# PET_Diag_Clip.net
KiCad netlist of a schematic drawn in EAGLE
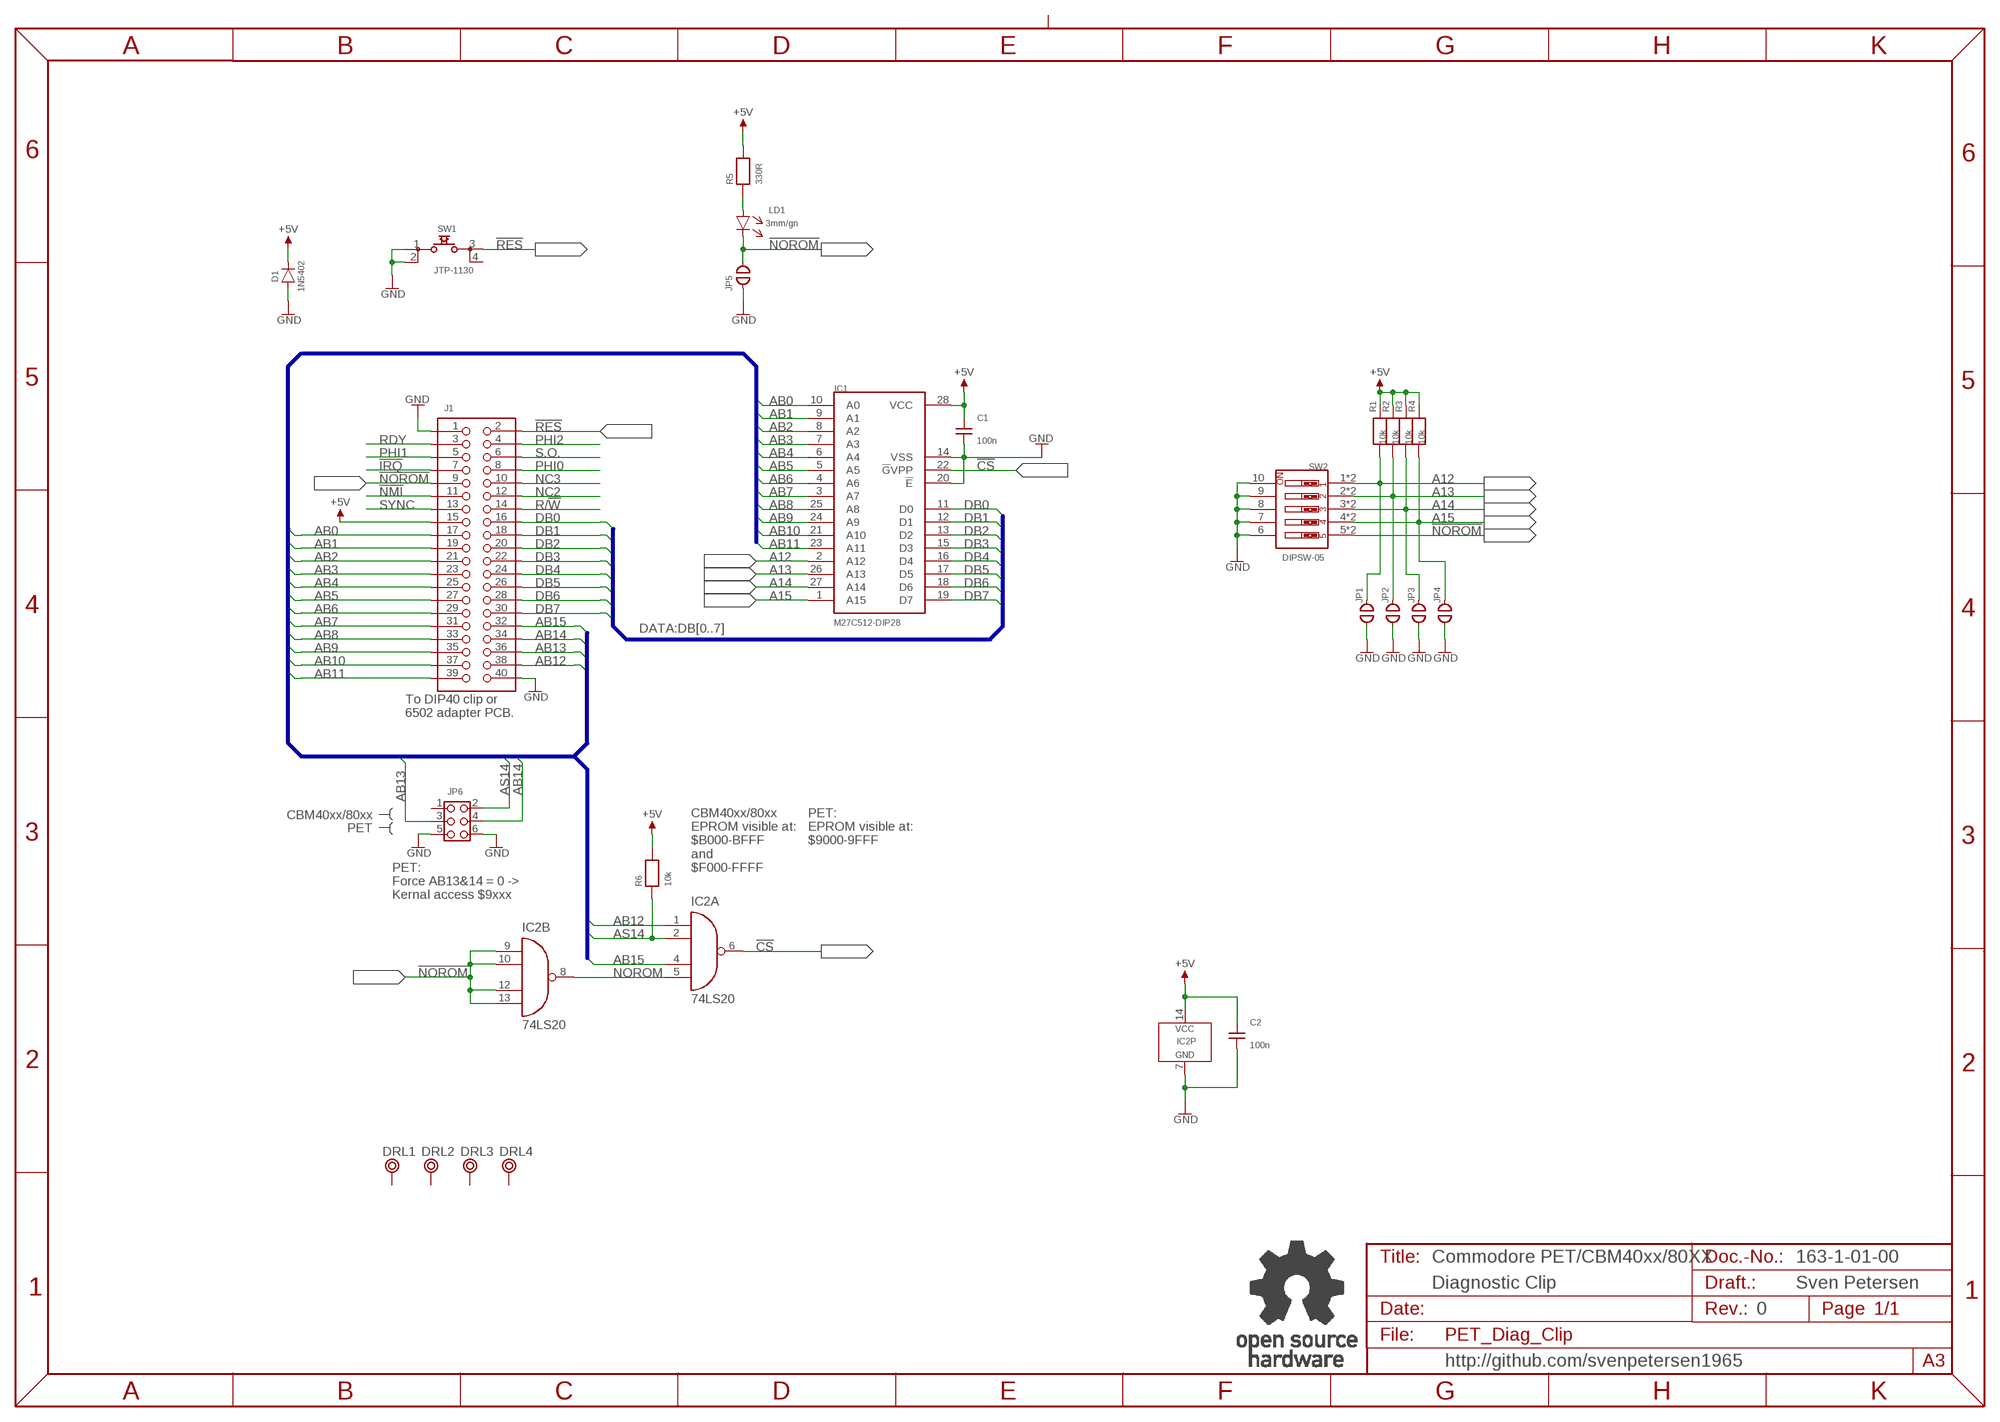
[diagram p0: schematic, sheet 1]

(export (version "E")
  (design (tool "Eeschema 10.0.6"))
  (components
    (comp (ref "C1")
      (value "100n")
      (footprint "eagle-import:C-2,5")
      (libsource (lib "eagle-import") (part "CAP01"))
    )
    (comp (ref "C2")
      (value "100n")
      (footprint "eagle-import:C-2,5")
      (libsource (lib "eagle-import") (part "CAP01"))
    )
    (comp (ref "D1")
      (value "1N5402")
      (footprint "eagle-import:DO-201")
      (libsource (lib "eagle-import") (part "1N5402"))
    )
    (comp (ref "DRL1")
      (value "BOHR3,5")
      (footprint "eagle-import:BOHR3,5")
      (libsource (lib "eagle-import") (part "BOHR3,5"))
    )
    (comp (ref "DRL2")
      (value "BOHR3,5")
      (footprint "eagle-import:BOHR3,5")
      (libsource (lib "eagle-import") (part "BOHR3,5"))
    )
    (comp (ref "DRL3")
      (value "BOHR3,5")
      (footprint "eagle-import:BOHR3,5")
      (libsource (lib "eagle-import") (part "BOHR3,5"))
    )
    (comp (ref "DRL4")
      (value "BOHR3,5")
      (footprint "eagle-import:BOHR3,5")
      (libsource (lib "eagle-import") (part "BOHR3,5"))
    )
    (comp (ref "IC1")
      (value "M27C512-DIP28")
      (footprint "eagle-import:DIL28-6")
      (libsource (lib "eagle-import") (part "M27C512-DIP28"))
    )
    (comp (ref "IC2")
      (value "74LS20")
      (footprint "eagle-import:DIL-14")
      (libsource (lib "eagle-import") (part "7420N"))
    )
    (comp (ref "J1")
      (value "PINHD-2X20WV")
      (footprint "eagle-import:2X20WV")
      (libsource (lib "eagle-import") (part "PINHD-2X20WV"))
    )
    (comp (ref "JP1")
      (value "OPEN")
      (footprint "eagle-import:CP_OP")
      (libsource (lib "eagle-import") (part "OPEN"))
    )
    (comp (ref "JP2")
      (value "OPEN")
      (footprint "eagle-import:CP_OP")
      (libsource (lib "eagle-import") (part "OPEN"))
    )
    (comp (ref "JP3")
      (value "OPEN")
      (footprint "eagle-import:CP_OP")
      (libsource (lib "eagle-import") (part "OPEN"))
    )
    (comp (ref "JP4")
      (value "OPEN")
      (footprint "eagle-import:CP_OP")
      (libsource (lib "eagle-import") (part "OPEN"))
    )
    (comp (ref "JP5")
      (value "COMBI_2P")
      (footprint "eagle-import:COMBI-2P")
      (libsource (lib "eagle-import") (part "COMBI_2P"))
    )
    (comp (ref "JP6")
      (value "JUMPER2X3")
      (footprint "eagle-import:2X03")
      (libsource (lib "eagle-import") (part "JUMPER2X3"))
    )
    (comp (ref "LD1")
      (value "3mm/gn")
      (footprint "eagle-import:3MM")
      (libsource (lib "eagle-import") (part "3MM"))
    )
    (comp (ref "R1")
      (value "10k")
      (footprint "eagle-import:R-10")
      (libsource (lib "eagle-import") (part "RES04"))
    )
    (comp (ref "R2")
      (value "10k")
      (footprint "eagle-import:R-10")
      (libsource (lib "eagle-import") (part "RES04"))
    )
    (comp (ref "R3")
      (value "10k")
      (footprint "eagle-import:R-10")
      (libsource (lib "eagle-import") (part "RES04"))
    )
    (comp (ref "R4")
      (value "10k")
      (footprint "eagle-import:R-10")
      (libsource (lib "eagle-import") (part "RES04"))
    )
    (comp (ref "R5")
      (value "330R")
      (footprint "eagle-import:R-10")
      (libsource (lib "eagle-import") (part "RES04"))
    )
    (comp (ref "R6")
      (value "10k")
      (footprint "eagle-import:R-10")
      (libsource (lib "eagle-import") (part "RES04"))
    )
    (comp (ref "SW1")
      (value "JTP-1130")
      (footprint "eagle-import:JTP-1130")
      (libsource (lib "eagle-import") (part "JTP-1130"))
    )
    (comp (ref "SW2")
      (value "DIPSW-05")
      (footprint "eagle-import:DIPSW-05VJ")
      (libsource (lib "eagle-import") (part "DIPSW-05"))
    )
    (comp (ref "U$13")
      (value "OPEN_SOURCE_HW")
      (footprint "eagle-import:OPENHW")
      (libsource (lib "eagle-import") (part "OPEN_SOURCE_HW"))
    )
  )
  (nets
    (net (code "9") (name "+5V") (class "Default")
      (node (ref "C1") (pin "2") (pinfunction "2_2") (pintype "passive"))
      (node (ref "C2") (pin "2") (pinfunction "2_2") (pintype "passive"))
      (node (ref "D1") (pin "K") (pinfunction "K_K") (pintype "passive"))
      (node (ref "IC1") (pin "28") (pinfunction "VCC_28") (pintype "power_in"))
      (node (ref "IC2") (pin "14") (pinfunction "VCC_14") (pintype "bidirectional"))
      (node (ref "J1") (pin "15") (pinfunction "15_15") (pintype "passive"))
      (node (ref "R1") (pin "1") (pinfunction "1_1") (pintype "passive"))
      (node (ref "R2") (pin "1") (pinfunction "1_1") (pintype "passive"))
      (node (ref "R3") (pin "1") (pinfunction "1_1") (pintype "passive"))
      (node (ref "R4") (pin "1") (pinfunction "1_1") (pintype "passive"))
      (node (ref "R5") (pin "2") (pinfunction "2_2") (pintype "passive"))
      (node (ref "R6") (pin "2") (pinfunction "2_2") (pintype "passive"))
    )
    (net (code "10") (name "/A12") (class "Default")
      (node (ref "IC1") (pin "2") (pinfunction "A12_2") (pintype "input"))
      (node (ref "JP1") (pin "2") (pinfunction "2_2") (pintype "passive"))
      (node (ref "R1") (pin "2") (pinfunction "2_2") (pintype "passive"))
      (node (ref "SW2") (pin "1") (pinfunction "1_1") (pintype "passive"))
      (node (ref "SW2") (pin "1J") (pinfunction "1_1J") (pintype "passive"))
    )
    (net (code "11") (name "/A13") (class "Default")
      (node (ref "IC1") (pin "26") (pinfunction "A13_26") (pintype "input"))
      (node (ref "JP2") (pin "2") (pinfunction "2_2") (pintype "passive"))
      (node (ref "R2") (pin "2") (pinfunction "2_2") (pintype "passive"))
      (node (ref "SW2") (pin "2") (pinfunction "2_2") (pintype "passive"))
      (node (ref "SW2") (pin "2J") (pinfunction "2_2J") (pintype "passive"))
    )
    (net (code "12") (name "/A14") (class "Default")
      (node (ref "IC1") (pin "27") (pinfunction "A14_27") (pintype "input"))
      (node (ref "JP3") (pin "2") (pinfunction "2_2") (pintype "passive"))
      (node (ref "R3") (pin "2") (pinfunction "2_2") (pintype "passive"))
      (node (ref "SW2") (pin "3") (pinfunction "3_3") (pintype "passive"))
      (node (ref "SW2") (pin "3J") (pinfunction "3_3J") (pintype "passive"))
    )
    (net (code "13") (name "/A15") (class "Default")
      (node (ref "IC1") (pin "1") (pinfunction "A15_1") (pintype "input"))
      (node (ref "JP4") (pin "2") (pinfunction "2_2") (pintype "passive"))
      (node (ref "R4") (pin "2") (pinfunction "2_2") (pintype "passive"))
      (node (ref "SW2") (pin "4") (pinfunction "4_4") (pintype "passive"))
      (node (ref "SW2") (pin "4J") (pinfunction "4_4J") (pintype "passive"))
    )
    (net (code "14") (name "/AB0") (class "Default")
      (node (ref "IC1") (pin "10") (pinfunction "A0_10") (pintype "input"))
      (node (ref "J1") (pin "17") (pinfunction "17_17") (pintype "passive"))
    )
    (net (code "15") (name "/AB1") (class "Default")
      (node (ref "IC1") (pin "9") (pinfunction "A1_9") (pintype "input"))
      (node (ref "J1") (pin "19") (pinfunction "19_19") (pintype "passive"))
    )
    (net (code "16") (name "/AB2") (class "Default")
      (node (ref "IC1") (pin "8") (pinfunction "A2_8") (pintype "input"))
      (node (ref "J1") (pin "21") (pinfunction "21_21") (pintype "passive"))
    )
    (net (code "17") (name "/AB3") (class "Default")
      (node (ref "IC1") (pin "7") (pinfunction "A3_7") (pintype "input"))
      (node (ref "J1") (pin "23") (pinfunction "23_23") (pintype "passive"))
    )
    (net (code "18") (name "/AB4") (class "Default")
      (node (ref "IC1") (pin "6") (pinfunction "A4_6") (pintype "input"))
      (node (ref "J1") (pin "25") (pinfunction "25_25") (pintype "passive"))
    )
    (net (code "19") (name "/AB5") (class "Default")
      (node (ref "IC1") (pin "5") (pinfunction "A5_5") (pintype "input"))
      (node (ref "J1") (pin "27") (pinfunction "27_27") (pintype "passive"))
    )
    (net (code "20") (name "/AB6") (class "Default")
      (node (ref "IC1") (pin "4") (pinfunction "A6_4") (pintype "input"))
      (node (ref "J1") (pin "29") (pinfunction "29_29") (pintype "passive"))
    )
    (net (code "21") (name "/AB7") (class "Default")
      (node (ref "IC1") (pin "3") (pinfunction "A7_3") (pintype "input"))
      (node (ref "J1") (pin "31") (pinfunction "31_31") (pintype "passive"))
    )
    (net (code "22") (name "/AB8") (class "Default")
      (node (ref "IC1") (pin "25") (pinfunction "A8_25") (pintype "input"))
      (node (ref "J1") (pin "33") (pinfunction "33_33") (pintype "passive"))
    )
    (net (code "23") (name "/AB9") (class "Default")
      (node (ref "IC1") (pin "24") (pinfunction "A9_24") (pintype "input"))
      (node (ref "J1") (pin "35") (pinfunction "35_35") (pintype "passive"))
    )
    (net (code "24") (name "/AB10") (class "Default")
      (node (ref "IC1") (pin "21") (pinfunction "A10_21") (pintype "input"))
      (node (ref "J1") (pin "37") (pinfunction "37_37") (pintype "passive"))
    )
    (net (code "25") (name "/AB11") (class "Default")
      (node (ref "IC1") (pin "23") (pinfunction "A11_23") (pintype "input"))
      (node (ref "J1") (pin "39") (pinfunction "39_39") (pintype "passive"))
    )
    (net (code "26") (name "/AB12") (class "Default")
      (node (ref "IC2") (pin "1") (pinfunction "I0_1") (pintype "input"))
      (node (ref "J1") (pin "38") (pinfunction "38_38") (pintype "passive"))
    )
    (net (code "27") (name "/AB13") (class "Default")
      (node (ref "J1") (pin "36") (pinfunction "36_36") (pintype "passive"))
      (node (ref "JP6") (pin "3") (pinfunction "3_3") (pintype "bidirectional"))
    )
    (net (code "28") (name "/AB14") (class "Default")
      (node (ref "J1") (pin "34") (pinfunction "34_34") (pintype "passive"))
      (node (ref "JP6") (pin "4") (pinfunction "4_4") (pintype "bidirectional"))
    )
    (net (code "29") (name "/AB15") (class "Default")
      (node (ref "IC2") (pin "4") (pinfunction "I2_4") (pintype "input"))
      (node (ref "J1") (pin "32") (pinfunction "32_32") (pintype "passive"))
    )
    (net (code "30") (name "/AS14") (class "Default")
      (node (ref "IC2") (pin "2") (pinfunction "I1_2") (pintype "input"))
      (node (ref "JP6") (pin "2") (pinfunction "2_2") (pintype "bidirectional"))
      (node (ref "R6") (pin "1") (pinfunction "1_1") (pintype "passive"))
    )
    (net (code "32") (name "/DB0") (class "Default")
      (node (ref "IC1") (pin "11") (pinfunction "D0_11") (pintype "bidirectional"))
      (node (ref "J1") (pin "16") (pinfunction "16_16") (pintype "passive"))
    )
    (net (code "33") (name "/DB1") (class "Default")
      (node (ref "IC1") (pin "12") (pinfunction "D1_12") (pintype "bidirectional"))
      (node (ref "J1") (pin "18") (pinfunction "18_18") (pintype "passive"))
    )
    (net (code "34") (name "/DB2") (class "Default")
      (node (ref "IC1") (pin "13") (pinfunction "D2_13") (pintype "bidirectional"))
      (node (ref "J1") (pin "20") (pinfunction "20_20") (pintype "passive"))
    )
    (net (code "35") (name "/DB3") (class "Default")
      (node (ref "IC1") (pin "15") (pinfunction "D3_15") (pintype "bidirectional"))
      (node (ref "J1") (pin "22") (pinfunction "22_22") (pintype "passive"))
    )
    (net (code "36") (name "/DB4") (class "Default")
      (node (ref "IC1") (pin "16") (pinfunction "D4_16") (pintype "bidirectional"))
      (node (ref "J1") (pin "24") (pinfunction "24_24") (pintype "passive"))
    )
    (net (code "37") (name "/DB5") (class "Default")
      (node (ref "IC1") (pin "17") (pinfunction "D5_17") (pintype "bidirectional"))
      (node (ref "J1") (pin "26") (pinfunction "26_26") (pintype "passive"))
    )
    (net (code "38") (name "/DB6") (class "Default")
      (node (ref "IC1") (pin "18") (pinfunction "D6_18") (pintype "bidirectional"))
      (node (ref "J1") (pin "28") (pinfunction "28_28") (pintype "passive"))
    )
    (net (code "39") (name "/DB7") (class "Default")
      (node (ref "IC1") (pin "19") (pinfunction "D7_19") (pintype "bidirectional"))
      (node (ref "J1") (pin "30") (pinfunction "30_30") (pintype "passive"))
    )
    (net (code "40") (name "/NC2") (class "Default")
      (node (ref "J1") (pin "12") (pinfunction "12_12") (pintype "passive"))
    )
    (net (code "41") (name "/NC3") (class "Default")
      (node (ref "J1") (pin "10") (pinfunction "10_10") (pintype "passive"))
    )
    (net (code "42") (name "/NOROM") (class "Default")
      (node (ref "IC2") (pin "5") (pinfunction "I3_5") (pintype "input"))
      (node (ref "IC2") (pin "8") (pinfunction "O_8") (pintype "output"))
    )
    (net (code "43") (name "/PHI0") (class "Default")
      (node (ref "J1") (pin "8") (pinfunction "8_8") (pintype "passive"))
    )
    (net (code "44") (name "/PHI1") (class "Default")
      (node (ref "J1") (pin "5") (pinfunction "5_5") (pintype "passive"))
    )
    (net (code "45") (name "/PHI2") (class "Default")
      (node (ref "J1") (pin "4") (pinfunction "4_4") (pintype "passive"))
    )
    (net (code "46") (name "/RDY") (class "Default")
      (node (ref "J1") (pin "3") (pinfunction "3_3") (pintype "passive"))
    )
    (net (code "47") (name "/R{slash}~{W}") (class "Default")
      (node (ref "J1") (pin "14") (pinfunction "14_14") (pintype "passive"))
    )
    (net (code "48") (name "/S.O.") (class "Default")
      (node (ref "J1") (pin "6") (pinfunction "6_6") (pintype "passive"))
    )
    (net (code "49") (name "/SYNC") (class "Default")
      (node (ref "J1") (pin "13") (pinfunction "13_13") (pintype "passive"))
    )
    (net (code "50") (name "/~{CS}") (class "Default")
      (node (ref "IC1") (pin "22") (pinfunction "~{G}VPP_22") (pintype "input"))
      (node (ref "IC2") (pin "6") (pinfunction "O_6") (pintype "output"))
    )
    (net (code "51") (name "/~{IRQ}") (class "Default")
      (node (ref "J1") (pin "7") (pinfunction "7_7") (pintype "passive"))
    )
    (net (code "52") (name "/~{NMI}") (class "Default")
      (node (ref "J1") (pin "11") (pinfunction "11_11") (pintype "passive"))
    )
    (net (code "53") (name "/~{NOROM}") (class "Default")
      (node (ref "IC2") (pin "10") (pinfunction "I1_10") (pintype "input"))
      (node (ref "IC2") (pin "12") (pinfunction "I2_12") (pintype "input"))
      (node (ref "IC2") (pin "13") (pinfunction "I3_13") (pintype "input"))
      (node (ref "IC2") (pin "9") (pinfunction "I0_9") (pintype "input"))
      (node (ref "J1") (pin "9") (pinfunction "9_9") (pintype "passive"))
      (node (ref "JP5") (pin "2") (pinfunction "2_2") (pintype "passive"))
      (node (ref "LD1") (pin "C") (pinfunction "K_C") (pintype "bidirectional"))
      (node (ref "SW2") (pin "5") (pinfunction "5_5") (pintype "passive"))
      (node (ref "SW2") (pin "5J") (pinfunction "5_5J") (pintype "passive"))
    )
    (net (code "54") (name "/~{RES}") (class "Default")
      (node (ref "J1") (pin "2") (pinfunction "2_2") (pintype "passive"))
      (node (ref "SW1") (pin "3") (pinfunction "3_3") (pintype "passive"))
    )
    (net (code "55") (name "GND") (class "Default")
      (node (ref "C1") (pin "1") (pinfunction "1_1") (pintype "passive"))
      (node (ref "C2") (pin "1") (pinfunction "1_1") (pintype "passive"))
      (node (ref "D1") (pin "A") (pinfunction "A_A") (pintype "passive"))
      (node (ref "IC1") (pin "14") (pinfunction "VSS_14") (pintype "power_in"))
      (node (ref "IC1") (pin "20") (pinfunction "~{E}_20") (pintype "input"))
      (node (ref "IC2") (pin "7") (pinfunction "GND_7") (pintype "bidirectional"))
      (node (ref "J1") (pin "1") (pinfunction "1_1") (pintype "passive"))
      (node (ref "J1") (pin "40") (pinfunction "40_40") (pintype "passive"))
      (node (ref "JP1") (pin "1") (pinfunction "1_1") (pintype "passive"))
      (node (ref "JP2") (pin "1") (pinfunction "1_1") (pintype "passive"))
      (node (ref "JP3") (pin "1") (pinfunction "1_1") (pintype "passive"))
      (node (ref "JP4") (pin "1") (pinfunction "1_1") (pintype "passive"))
      (node (ref "JP5") (pin "1") (pinfunction "1_1") (pintype "passive"))
      (node (ref "JP6") (pin "5") (pinfunction "5_5") (pintype "bidirectional"))
      (node (ref "JP6") (pin "6") (pinfunction "6_6") (pintype "bidirectional"))
      (node (ref "SW1") (pin "1") (pinfunction "1_1") (pintype "passive"))
      (node (ref "SW1") (pin "2") (pinfunction "2_2") (pintype "passive"))
      (node (ref "SW2") (pin "10") (pinfunction "10_10") (pintype "passive"))
      (node (ref "SW2") (pin "6") (pinfunction "6_6") (pintype "passive"))
      (node (ref "SW2") (pin "7") (pinfunction "7_7") (pintype "passive"))
      (node (ref "SW2") (pin "8") (pinfunction "8_8") (pintype "passive"))
      (node (ref "SW2") (pin "9") (pinfunction "9_9") (pintype "passive"))
    )
    (net (code "56") (name "Net-(LD1-PadA)") (class "Default")
      (node (ref "LD1") (pin "A") (pinfunction "A_A") (pintype "bidirectional"))
      (node (ref "R5") (pin "1") (pinfunction "1_1") (pintype "passive"))
    )
    (net (code "57") (name "unconnected-(DRL1-PadP$1)") (class "Default")
      (node (ref "DRL1") (pin "P$1") (pinfunction "P$1_P$1") (pintype "passive"))
    )
    (net (code "58") (name "unconnected-(DRL2-PadP$1)") (class "Default")
      (node (ref "DRL2") (pin "P$1") (pinfunction "P$1_P$1") (pintype "passive"))
    )
    (net (code "59") (name "unconnected-(DRL3-PadP$1)") (class "Default")
      (node (ref "DRL3") (pin "P$1") (pinfunction "P$1_P$1") (pintype "passive"))
    )
    (net (code "60") (name "unconnected-(DRL4-PadP$1)") (class "Default")
      (node (ref "DRL4") (pin "P$1") (pinfunction "P$1_P$1") (pintype "passive"))
    )
    (net (code "61") (name "unconnected-(JP6-Pad1)") (class "Default")
      (node (ref "JP6") (pin "1") (pinfunction "1_1") (pintype "bidirectional"))
    )
    (net (code "62") (name "unconnected-(SW1-Pad4)") (class "Default")
      (node (ref "SW1") (pin "4") (pinfunction "4_4") (pintype "passive"))
    )
  )
)
